# Baropodometro_V3.net
KiCad netlist of a schematic drawn in EAGLE
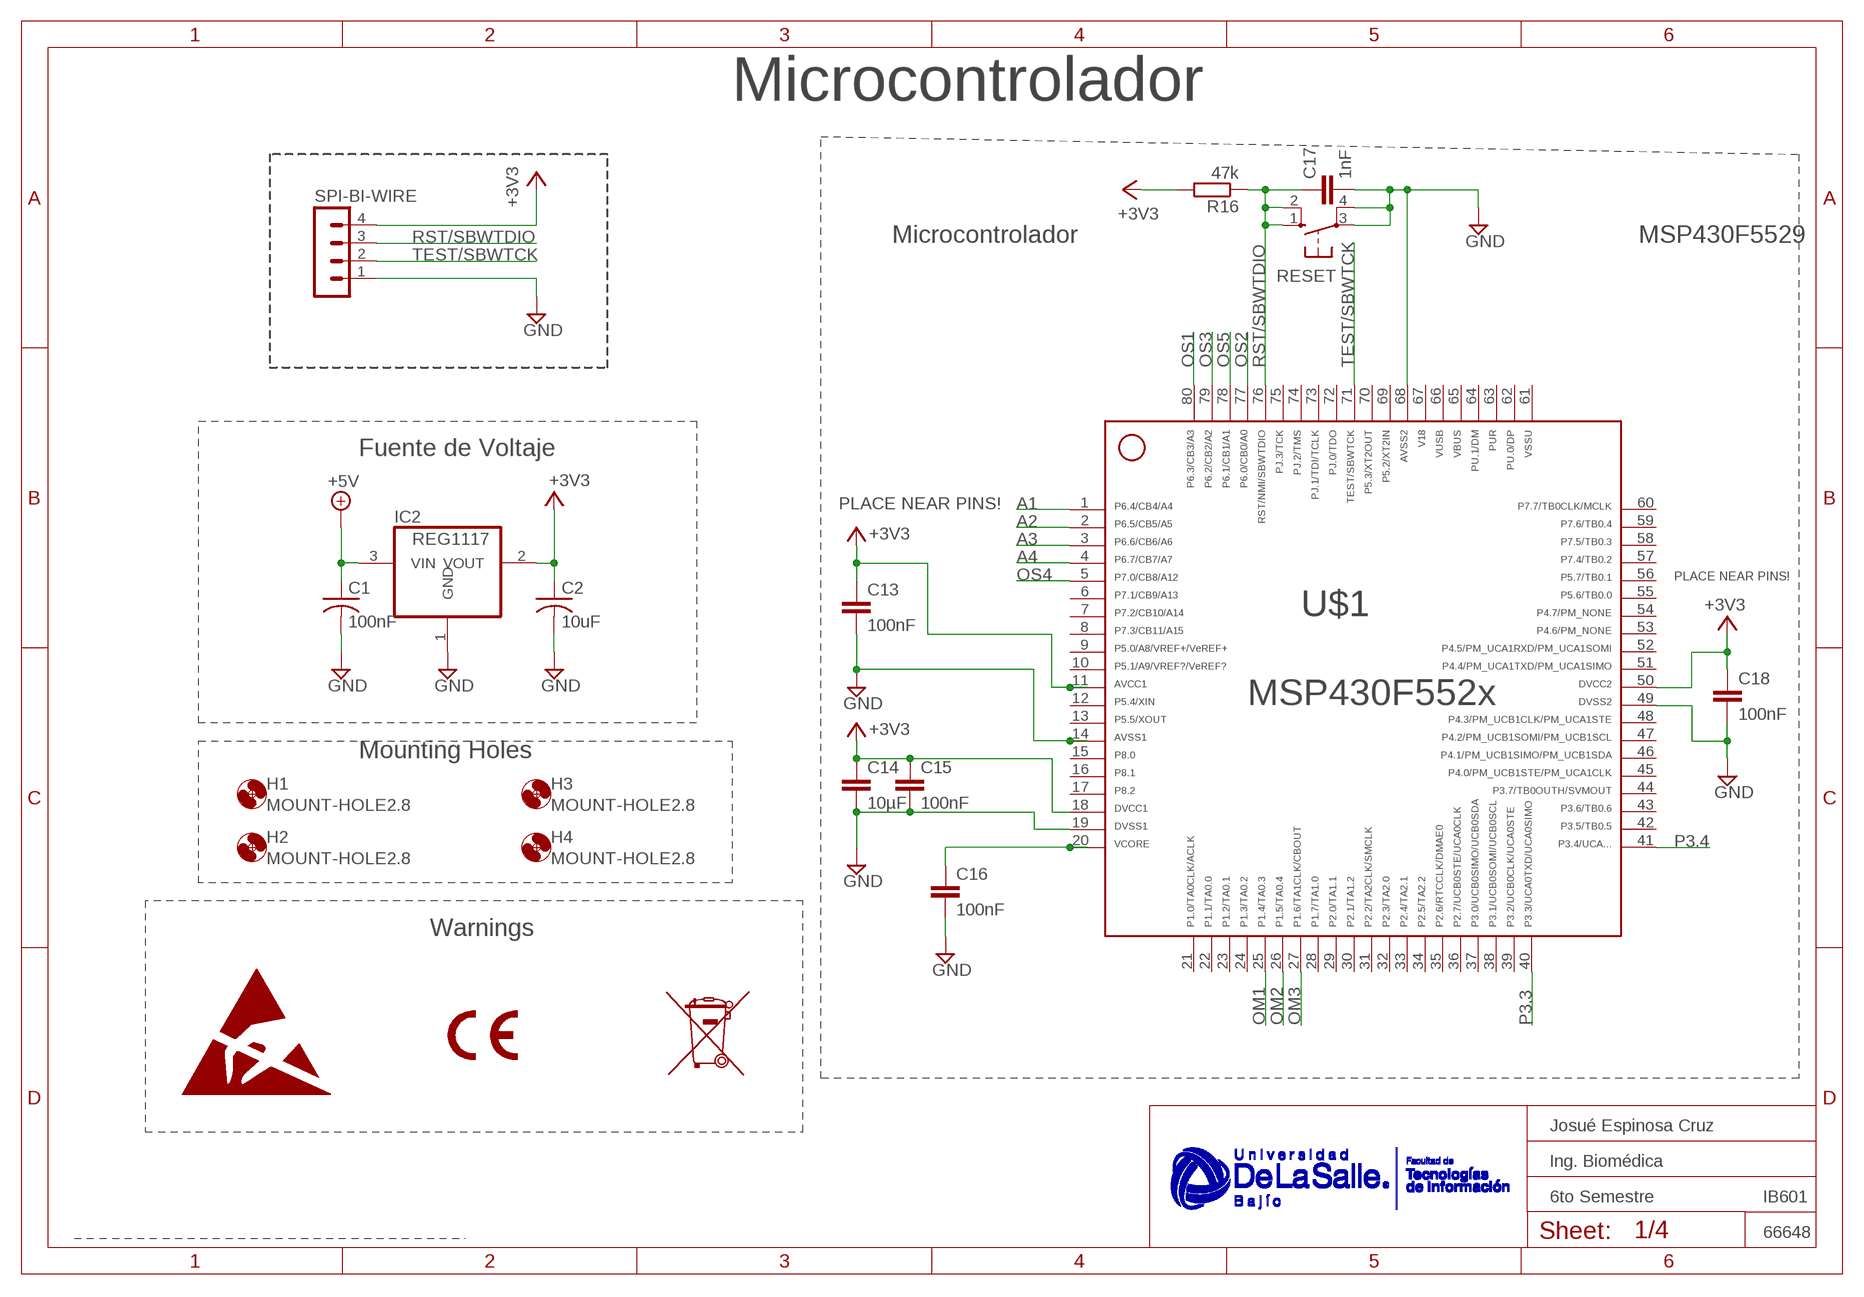
[diagram p0: schematic, sheet 1]
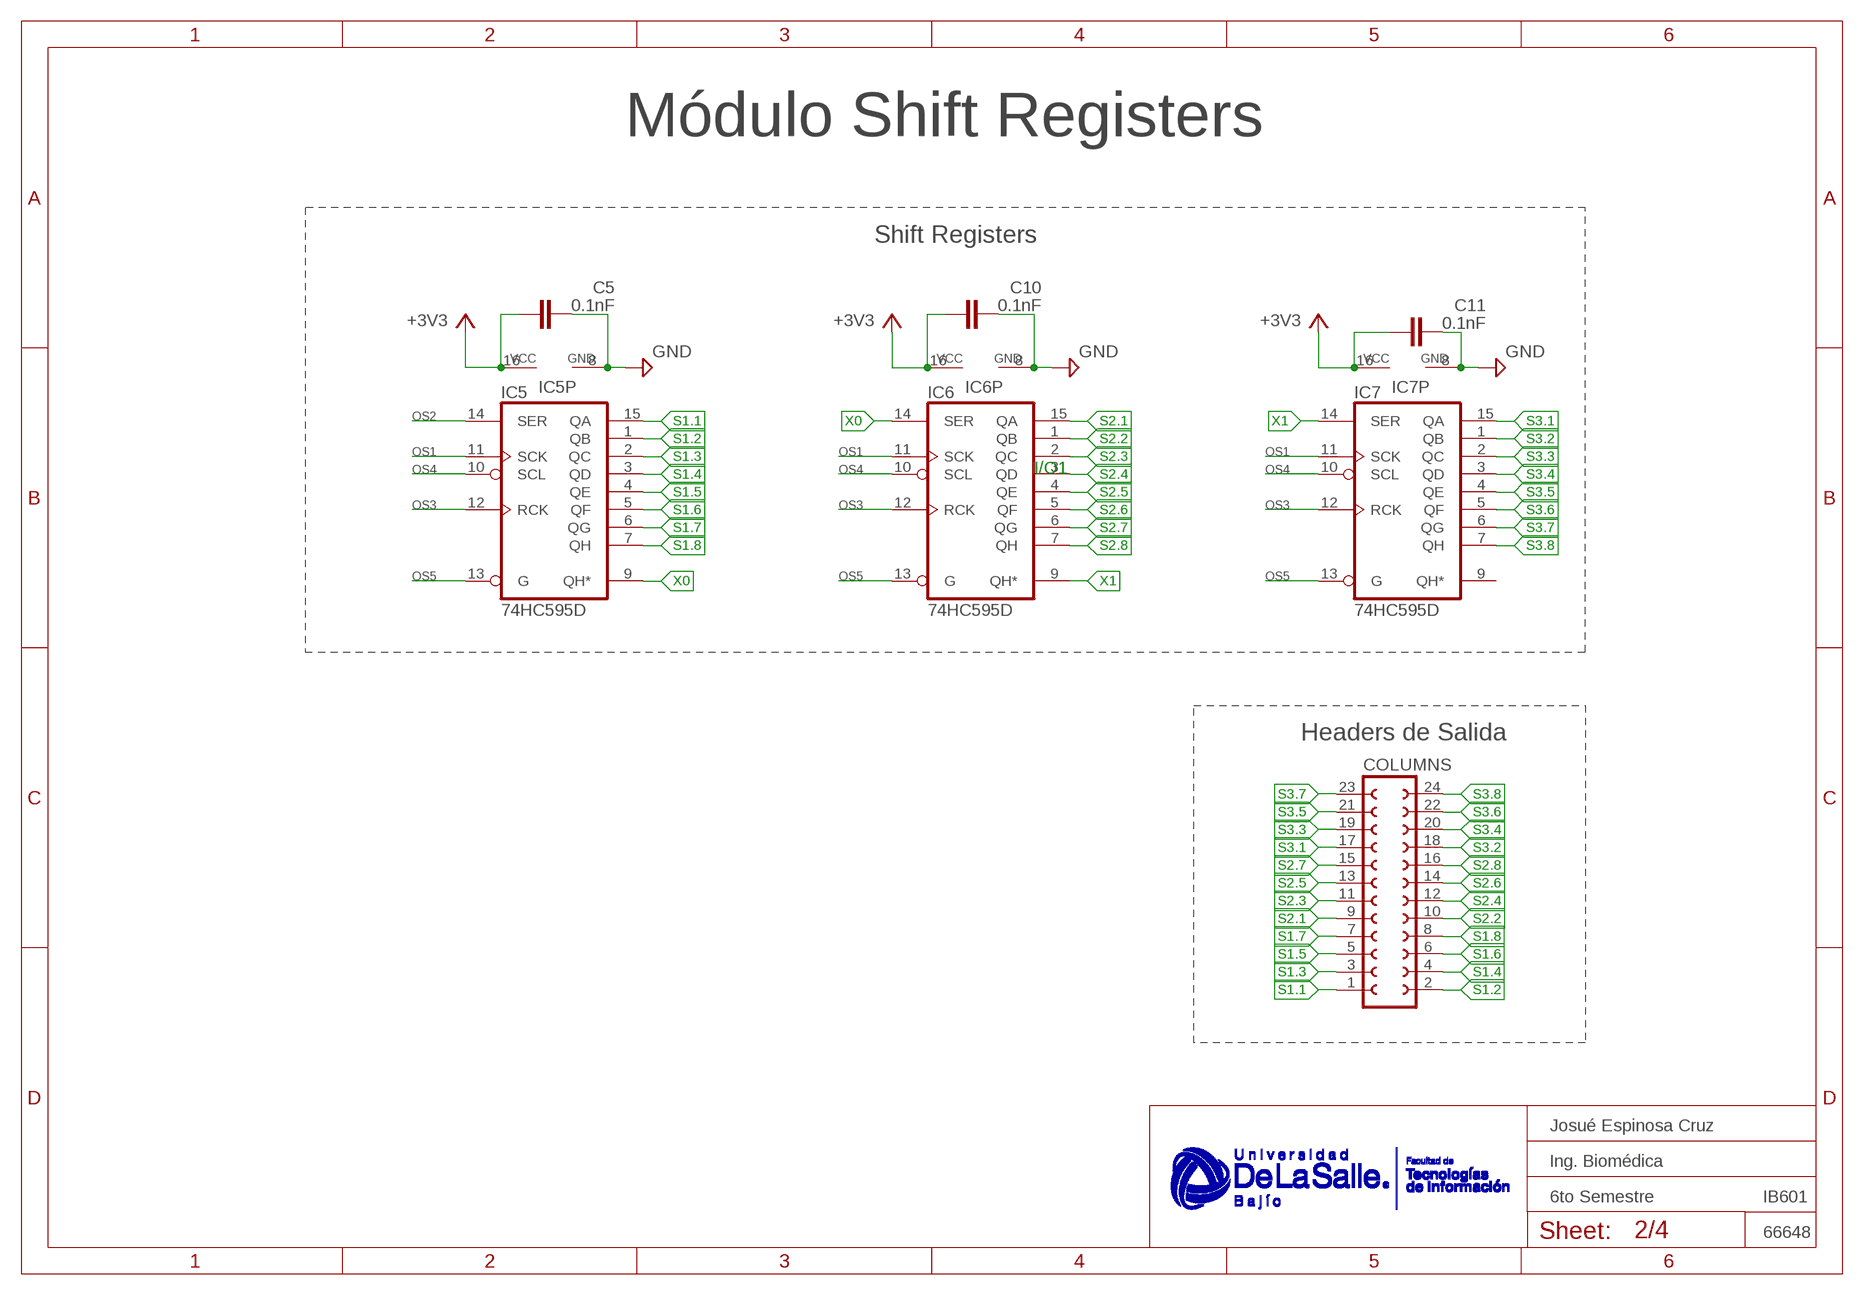
[diagram p1: schematic, sheet 2]
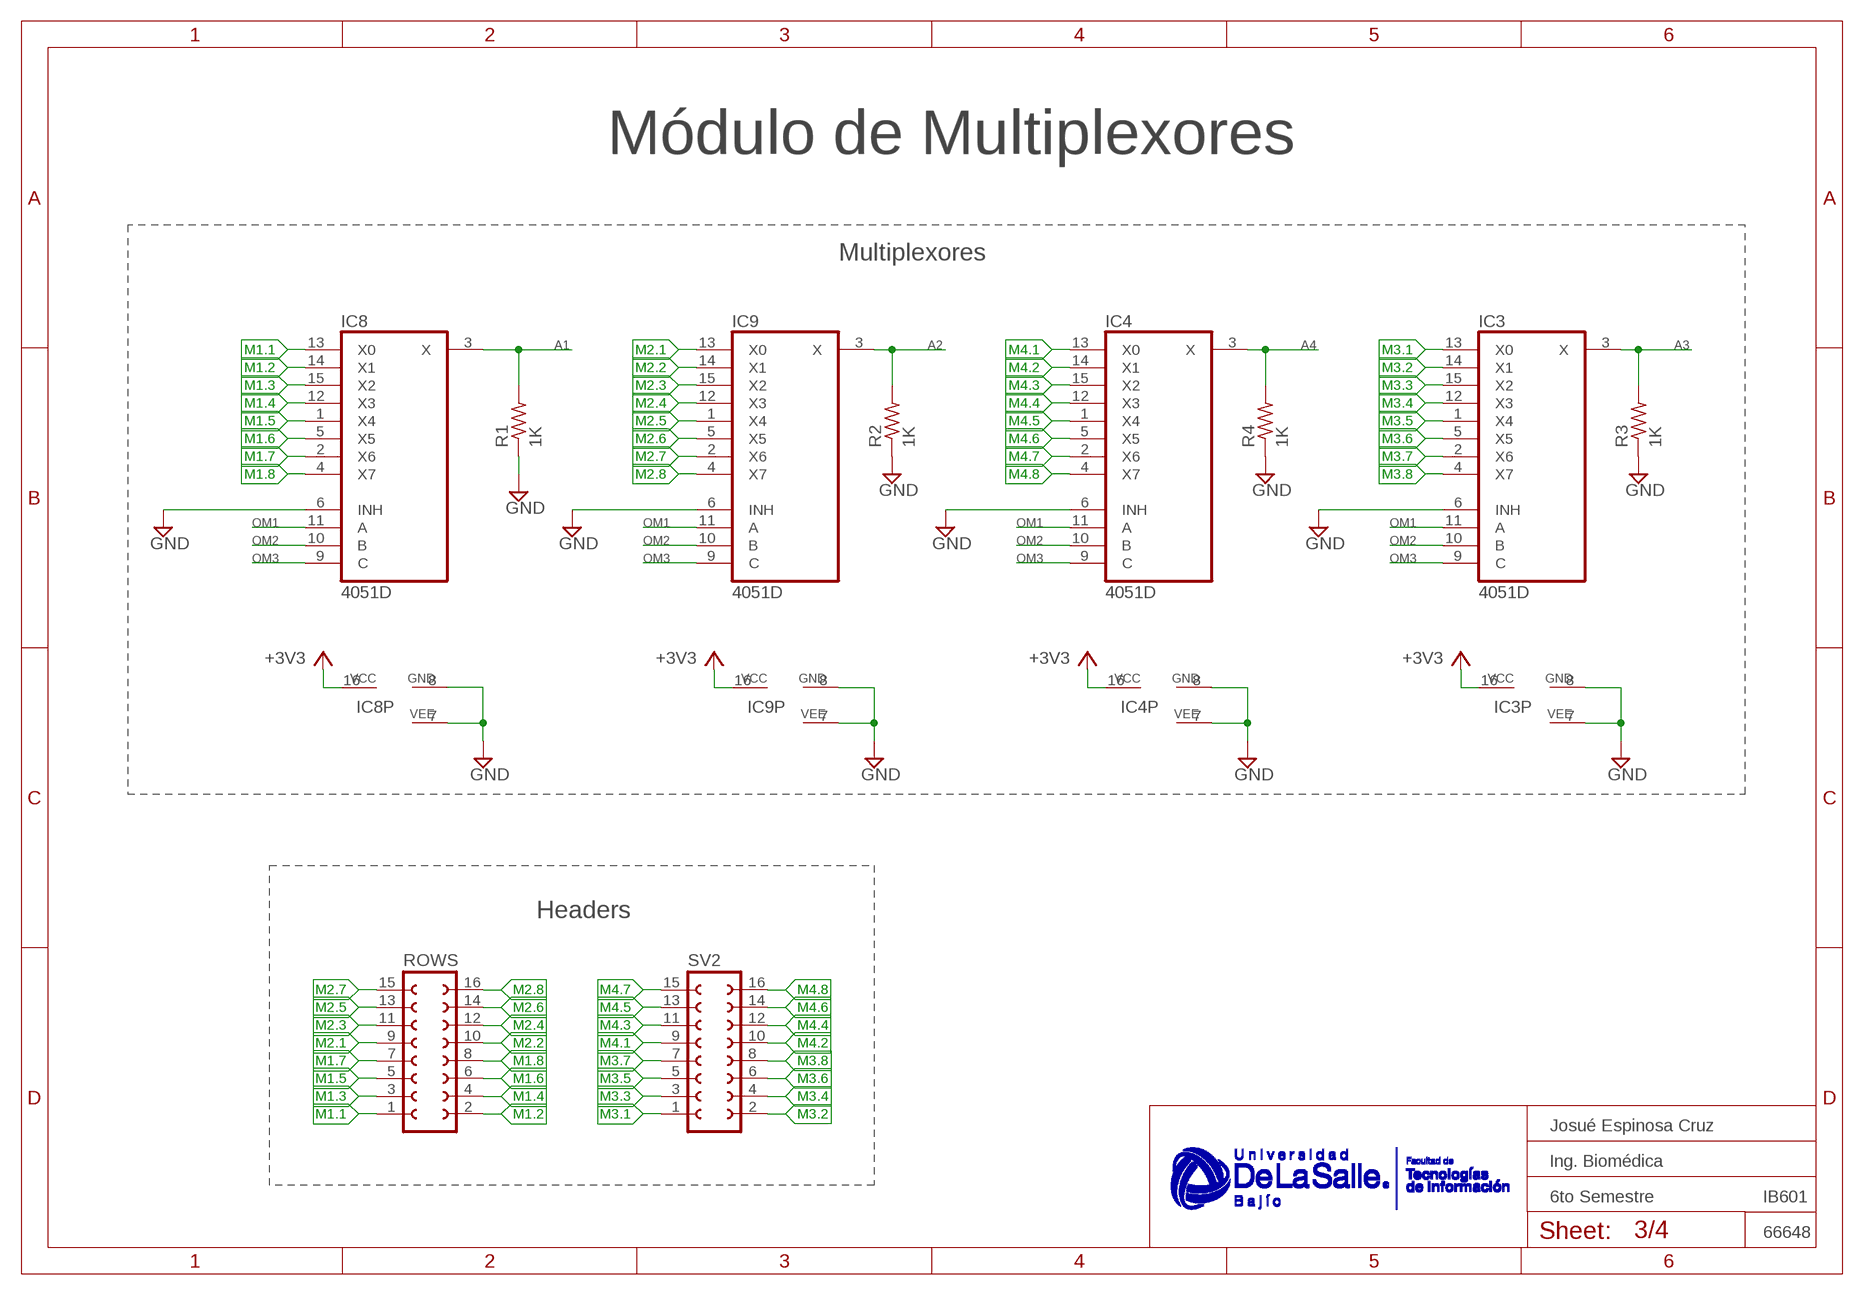
[diagram p2: schematic, sheet 3]
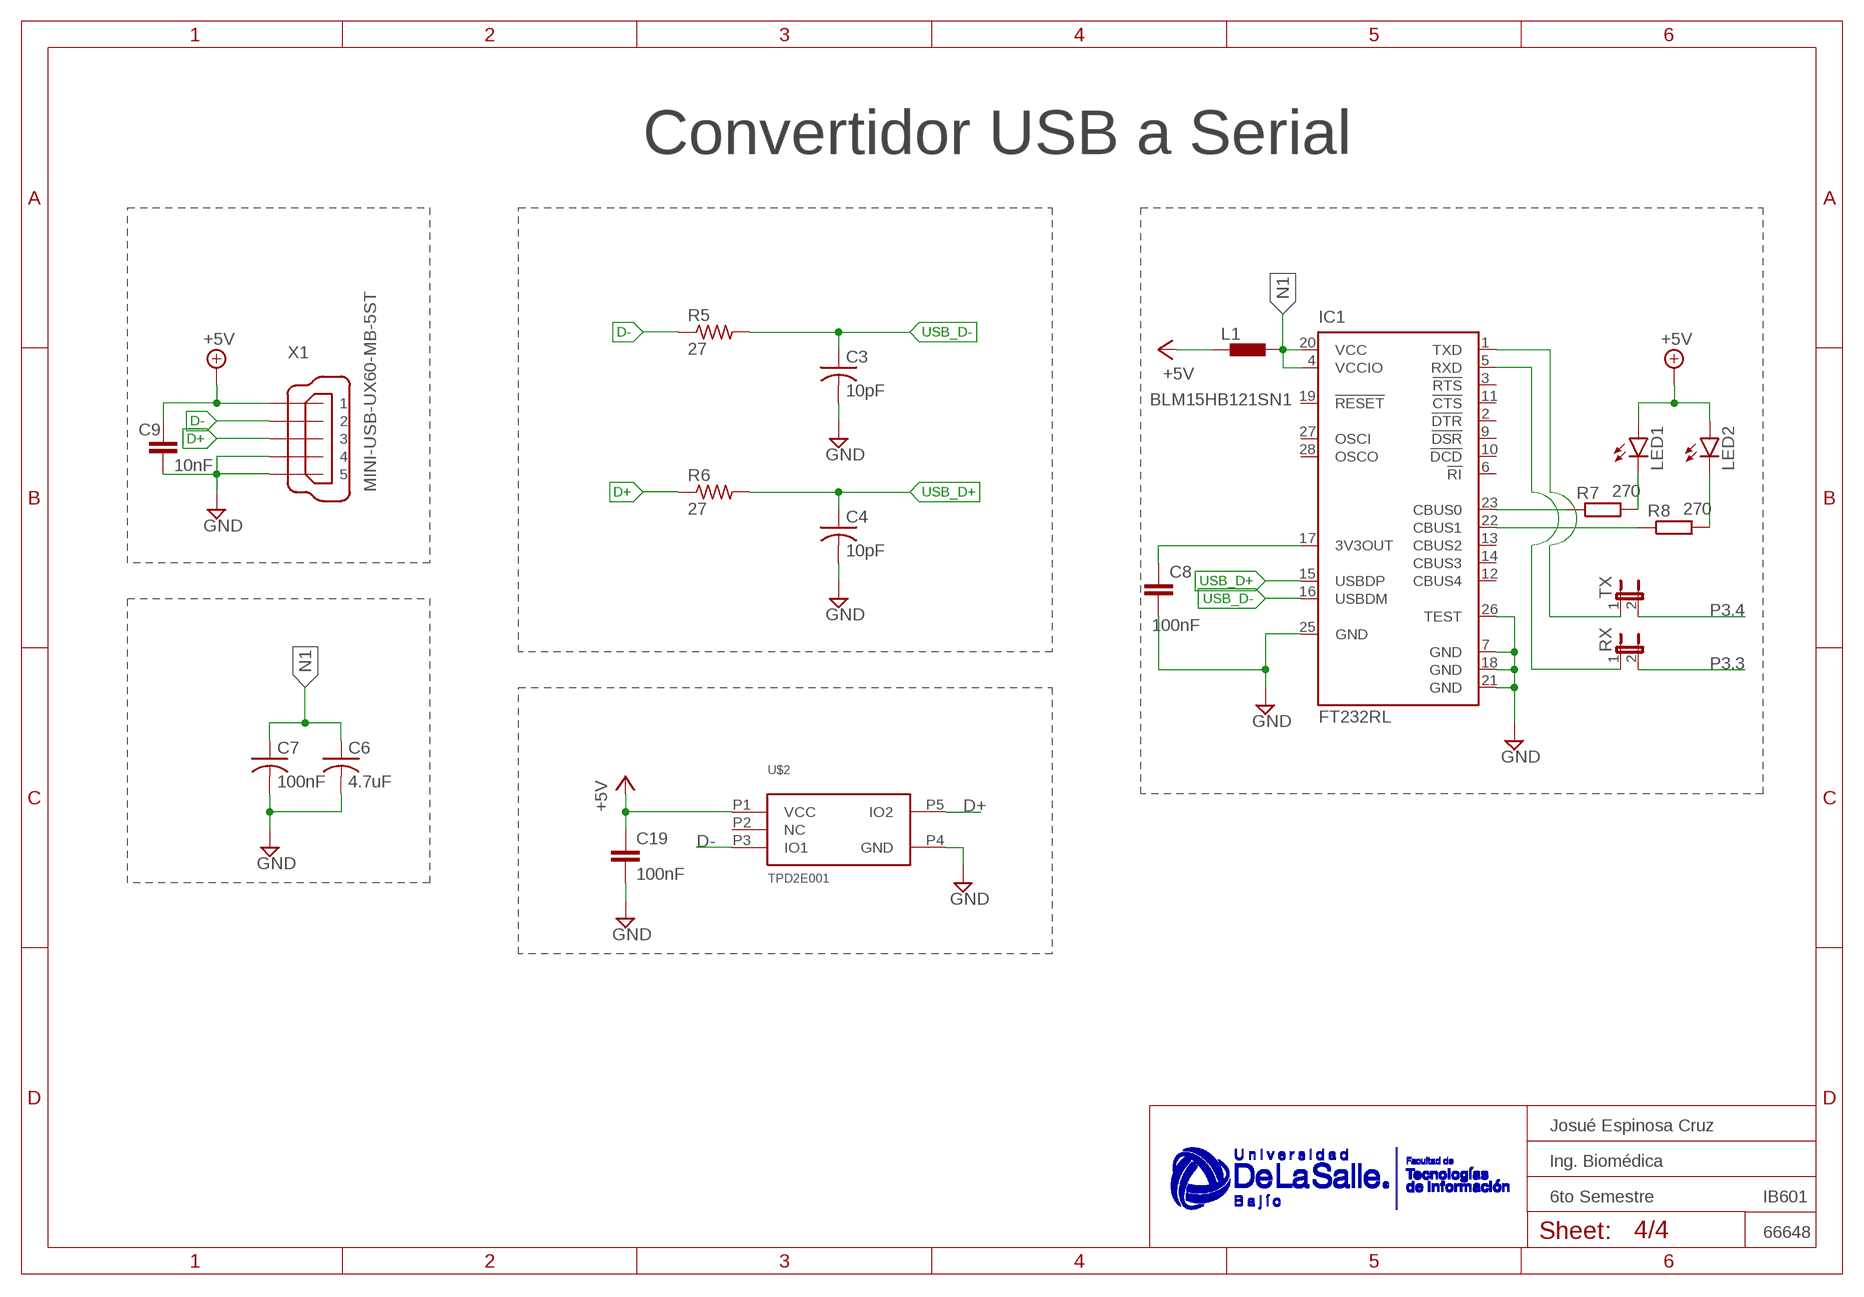
[diagram p3: schematic, sheet 4]

(export (version "E")
  (design (tool "Eeschema 10.0.6"))
  (components
    (comp (ref "C3")
      (value "10pF")
      (footprint "eagle-import:C0805")
      (libsource (lib "eagle-import") (part "C-USC0805"))
    )
    (comp (ref "C4")
      (value "10pF")
      (footprint "eagle-import:C0805")
      (libsource (lib "eagle-import") (part "C-USC0805"))
    )
    (comp (ref "C6")
      (value "4.7uF")
      (footprint "eagle-import:C0805")
      (libsource (lib "eagle-import") (part "C-USC0805"))
    )
    (comp (ref "C7")
      (value "100nF")
      (footprint "eagle-import:C0805")
      (libsource (lib "eagle-import") (part "C-USC0805"))
    )
    (comp (ref "C8")
      (value "100nF")
      (footprint "eagle-import:C0805")
      (libsource (lib "eagle-import") (part "C-EUC0805"))
    )
    (comp (ref "C9")
      (value "10nF")
      (footprint "eagle-import:C0805")
      (libsource (lib "eagle-import") (part "C-EUC0805"))
    )
    (comp (ref "C19")
      (value "100nF")
      (footprint "eagle-import:C0805")
      (libsource (lib "eagle-import") (part "C-EUC0805"))
    )
    (comp (ref "IC1")
      (value "FT232RL")
      (footprint "eagle-import:SSOP28")
      (libsource (lib "eagle-import") (part "FT232RL"))
    )
    (comp (ref "L1")
      (value "BLM15HB121SN1")
      (footprint "eagle-import:0402")
      (libsource (lib "eagle-import") (part "BLM15HB121SN1"))
    )
    (comp (ref "LED1")
      (value "LEDCHIP-LED0805")
      (footprint "eagle-import:CHIP-LED0805")
      (libsource (lib "eagle-import") (part "LEDCHIP-LED0805"))
    )
    (comp (ref "LED2")
      (value "LEDCHIP-LED0805")
      (footprint "eagle-import:CHIP-LED0805")
      (libsource (lib "eagle-import") (part "LEDCHIP-LED0805"))
    )
    (comp (ref "R5")
      (value "27")
      (footprint "eagle-import:R0805")
      (libsource (lib "eagle-import") (part "R-US_R0805"))
    )
    (comp (ref "R6")
      (value "27")
      (footprint "eagle-import:R0805")
      (libsource (lib "eagle-import") (part "R-US_R0805"))
    )
    (comp (ref "R7")
      (value "270")
      (footprint "eagle-import:R0805")
      (libsource (lib "eagle-import") (part "R-EU_R0805"))
    )
    (comp (ref "R8")
      (value "270")
      (footprint "eagle-import:R0805")
      (libsource (lib "eagle-import") (part "R-EU_R0805"))
    )
    (comp (ref "RX")
      (value "JP1E")
      (footprint "eagle-import:JP1")
      (libsource (lib "eagle-import") (part "JP1E"))
    )
    (comp (ref "TX")
      (value "JP1E")
      (footprint "eagle-import:JP1")
      (libsource (lib "eagle-import") (part "JP1E"))
    )
    (comp (ref "U$2")
      (value "TPD2E001")
      (footprint "eagle-import:SOT-5")
      (libsource (lib "eagle-import") (part "TPD2E001"))
    )
    (comp (ref "X1")
      (value "MINI-USB-UX60-MB-5ST")
      (footprint "eagle-import:UX60-MB-5ST")
      (libsource (lib "eagle-import") (part "MINI-USB-UX60-MB-5ST"))
    )
    (comp (ref "C5")
      (value "0.1nF")
      (footprint "eagle-import:C0805")
      (libsource (lib "eagle-import") (part "C-EUC0805"))
    )
    (comp (ref "C10")
      (value "0.1nF")
      (footprint "eagle-import:C0805")
      (libsource (lib "eagle-import") (part "C-EUC0805"))
    )
    (comp (ref "C11")
      (value "0.1nF")
      (footprint "eagle-import:C0805")
      (libsource (lib "eagle-import") (part "C-EUC0805"))
    )
    (comp (ref "COLUMNS")
      (value "FE12-2W")
      (footprint "eagle-import:FE12-2W")
      (libsource (lib "eagle-import") (part "FE12-2W"))
    )
    (comp (ref "IC5")
      (value "74HC595D")
      (footprint "eagle-import:SO16")
      (libsource (lib "eagle-import") (part "74595DHC"))
    )
    (comp (ref "IC6")
      (value "74HC595D")
      (footprint "eagle-import:SO16")
      (libsource (lib "eagle-import") (part "74595DHC"))
    )
    (comp (ref "IC7")
      (value "74HC595D")
      (footprint "eagle-import:SO16")
      (libsource (lib "eagle-import") (part "74595DHC"))
    )
    (comp (ref "C1")
      (value "100nF")
      (footprint "eagle-import:C0805")
      (libsource (lib "eagle-import") (part "C-USC0805"))
    )
    (comp (ref "C2")
      (value "10uF")
      (footprint "eagle-import:C0805")
      (libsource (lib "eagle-import") (part "C-USC0805"))
    )
    (comp (ref "C13")
      (value "100nF")
      (footprint "eagle-import:C0805")
      (libsource (lib "eagle-import") (part "C-EUC0805"))
    )
    (comp (ref "C14")
      (value "10µF")
      (footprint "eagle-import:C0805")
      (libsource (lib "eagle-import") (part "C-EUC0805"))
    )
    (comp (ref "C15")
      (value "100nF")
      (footprint "eagle-import:C0805")
      (libsource (lib "eagle-import") (part "C-EUC0805"))
    )
    (comp (ref "C16")
      (value "100nF")
      (footprint "eagle-import:C0805")
      (libsource (lib "eagle-import") (part "C-EUC0805"))
    )
    (comp (ref "C17")
      (value "1nF")
      (footprint "eagle-import:C0805")
      (libsource (lib "eagle-import") (part "C-EUC0805"))
    )
    (comp (ref "C18")
      (value "100nF")
      (footprint "eagle-import:C0805")
      (libsource (lib "eagle-import") (part "C-EUC0805"))
    )
    (comp (ref "H1")
      (value "MOUNT-HOLE2.8")
      (footprint "eagle-import:2,8")
      (libsource (lib "eagle-import") (part "MOUNT-HOLE2.8"))
    )
    (comp (ref "H2")
      (value "MOUNT-HOLE2.8")
      (footprint "eagle-import:2,8")
      (libsource (lib "eagle-import") (part "MOUNT-HOLE2.8"))
    )
    (comp (ref "H3")
      (value "MOUNT-HOLE2.8")
      (footprint "eagle-import:2,8")
      (libsource (lib "eagle-import") (part "MOUNT-HOLE2.8"))
    )
    (comp (ref "H4")
      (value "MOUNT-HOLE2.8")
      (footprint "eagle-import:2,8")
      (libsource (lib "eagle-import") (part "MOUNT-HOLE2.8"))
    )
    (comp (ref "IC2")
      (value "REG1117")
      (footprint "eagle-import:SOT223")
      (libsource (lib "eagle-import") (part "REG1117"))
    )
    (comp (ref "R16")
      (value "47k")
      (footprint "eagle-import:R0805")
      (libsource (lib "eagle-import") (part "R-EU_R0805"))
    )
    (comp (ref "RESET")
      (value "10-XX")
      (footprint "eagle-import:B3F-10XX")
      (fields (field (name "MPN") "B3F-1000"))
      (libsource (lib "eagle-import") (part "10-XX"))
    )
    (comp (ref "SPI-BI-WIRE")
      (value "MA04-1")
      (footprint "eagle-import:MA04-1")
      (libsource (lib "eagle-import") (part "MA04-1"))
    )
    (comp (ref "U$1")
      (value "MSP430F5529")
      (footprint "eagle-import:TI_MSP430_V16_INTERN_PN80")
      (libsource (lib "eagle-import") (part "TI_MSP430_V16_INTERN_F552X---PN80"))
    )
    (comp (ref "IC3")
      (value "4051D")
      (footprint "eagle-import:SO16")
      (libsource (lib "eagle-import") (part "4051D"))
    )
    (comp (ref "IC4")
      (value "4051D")
      (footprint "eagle-import:SO16")
      (libsource (lib "eagle-import") (part "4051D"))
    )
    (comp (ref "IC8")
      (value "4051D")
      (footprint "eagle-import:SO16")
      (libsource (lib "eagle-import") (part "4051D"))
    )
    (comp (ref "IC9")
      (value "4051D")
      (footprint "eagle-import:SO16")
      (libsource (lib "eagle-import") (part "4051D"))
    )
    (comp (ref "R1")
      (value "1K")
      (footprint "eagle-import:R0805")
      (libsource (lib "eagle-import") (part "R-US_R0805"))
    )
    (comp (ref "R2")
      (value "1K")
      (footprint "eagle-import:R0805")
      (libsource (lib "eagle-import") (part "R-US_R0805"))
    )
    (comp (ref "R3")
      (value "1K")
      (footprint "eagle-import:R0805")
      (libsource (lib "eagle-import") (part "R-US_R0805"))
    )
    (comp (ref "R4")
      (value "1K")
      (footprint "eagle-import:R0805")
      (libsource (lib "eagle-import") (part "R-US_R0805"))
    )
    (comp (ref "ROWS")
      (value "FE08-2W")
      (footprint "eagle-import:FE08-2W")
      (libsource (lib "eagle-import") (part "FE08-2W"))
    )
    (comp (ref "SV2")
      (value "FE08-2W")
      (footprint "eagle-import:FE08-2W")
      (libsource (lib "eagle-import") (part "FE08-2W"))
    )
  )
  (nets
    (net (code "1") (name "+3V3") (class "Default")
      (node (ref "C10") (pin "1") (pinfunction "1_1") (pintype "passive"))
      (node (ref "C11") (pin "1") (pinfunction "1_1") (pintype "passive"))
      (node (ref "C13") (pin "1") (pinfunction "1_1") (pintype "passive"))
      (node (ref "C14") (pin "1") (pinfunction "1_1") (pintype "passive"))
      (node (ref "C15") (pin "1") (pinfunction "1_1") (pintype "passive"))
      (node (ref "C18") (pin "1") (pinfunction "1_1") (pintype "passive"))
      (node (ref "C2") (pin "1") (pinfunction "1_1") (pintype "passive"))
      (node (ref "C5") (pin "1") (pinfunction "1_1") (pintype "passive"))
      (node (ref "IC2") (pin "2") (pinfunction "VOUT_2") (pintype "output"))
      (node (ref "IC3") (pin "16") (pinfunction "VCC_16") (pintype "power_in"))
      (node (ref "IC4") (pin "16") (pinfunction "VCC_16") (pintype "power_in"))
      (node (ref "IC5") (pin "16") (pinfunction "VCC_16") (pintype "power_in"))
      (node (ref "IC6") (pin "16") (pinfunction "VCC_16") (pintype "power_in"))
      (node (ref "IC7") (pin "16") (pinfunction "VCC_16") (pintype "power_in"))
      (node (ref "IC8") (pin "16") (pinfunction "VCC_16") (pintype "power_in"))
      (node (ref "IC9") (pin "16") (pinfunction "VCC_16") (pintype "power_in"))
      (node (ref "R16") (pin "2") (pinfunction "2_2") (pintype "passive"))
      (node (ref "SPI-BI-WIRE") (pin "4") (pinfunction "4_4") (pintype "passive"))
      (node (ref "U$1") (pin "11") (pinfunction "11_11") (pintype "power_in"))
      (node (ref "U$1") (pin "18") (pinfunction "18_18") (pintype "power_in"))
      (node (ref "U$1") (pin "50") (pinfunction "50_50") (pintype "power_in"))
    )
    (net (code "2") (name "+5V") (class "Default")
      (node (ref "C1") (pin "1") (pinfunction "1_1") (pintype "passive"))
      (node (ref "C19") (pin "1") (pinfunction "1_1") (pintype "passive"))
      (node (ref "C9") (pin "1") (pinfunction "1_1") (pintype "passive"))
      (node (ref "IC2") (pin "3") (pinfunction "VIN_3") (pintype "input"))
      (node (ref "L1") (pin "1") (pinfunction "1_1") (pintype "passive"))
      (node (ref "LED1") (pin "A") (pinfunction "A_A") (pintype "passive"))
      (node (ref "LED2") (pin "A") (pinfunction "A_A") (pintype "passive"))
      (node (ref "U$2") (pin "P1") (pinfunction "VCC_P1") (pintype "bidirectional"))
      (node (ref "X1") (pin "1") (pinfunction "1_1") (pintype "input"))
    )
    (net (code "3") (name "61") (class "Default")
      (node (ref "U$1") (pin "61") (pinfunction "61_61") (pintype "power_in"))
    )
    (net (code "4") (name "65") (class "Default")
      (node (ref "U$1") (pin "65") (pinfunction "65_65") (pintype "power_in"))
    )
    (net (code "5") (name "66") (class "Default")
      (node (ref "U$1") (pin "66") (pinfunction "66_66") (pintype "power_in"))
    )
    (net (code "6") (name "67") (class "Default")
      (node (ref "U$1") (pin "67") (pinfunction "67_67") (pintype "power_in"))
    )
    (net (code "7") (name "A1") (class "Default")
      (node (ref "IC8") (pin "3") (pinfunction "X_3") (pintype "bidirectional"))
      (node (ref "R1") (pin "2") (pinfunction "2_2") (pintype "passive"))
      (node (ref "U$1") (pin "1") (pinfunction "1_1") (pintype "bidirectional"))
    )
    (net (code "8") (name "A2") (class "Default")
      (node (ref "IC9") (pin "3") (pinfunction "X_3") (pintype "bidirectional"))
      (node (ref "R2") (pin "2") (pinfunction "2_2") (pintype "passive"))
      (node (ref "U$1") (pin "2") (pinfunction "2_2") (pintype "bidirectional"))
    )
    (net (code "9") (name "A3") (class "Default")
      (node (ref "IC3") (pin "3") (pinfunction "X_3") (pintype "bidirectional"))
      (node (ref "R3") (pin "2") (pinfunction "2_2") (pintype "passive"))
      (node (ref "U$1") (pin "3") (pinfunction "3_3") (pintype "bidirectional"))
    )
    (net (code "10") (name "A4") (class "Default")
      (node (ref "IC4") (pin "3") (pinfunction "X_3") (pintype "bidirectional"))
      (node (ref "R4") (pin "2") (pinfunction "2_2") (pintype "passive"))
      (node (ref "U$1") (pin "4") (pinfunction "4_4") (pintype "bidirectional"))
    )
    (net (code "11") (name "D+") (class "Default")
      (node (ref "R6") (pin "1") (pinfunction "1_1") (pintype "passive"))
      (node (ref "U$2") (pin "P5") (pinfunction "IO2_P5") (pintype "bidirectional"))
      (node (ref "X1") (pin "3") (pinfunction "3_3") (pintype "input"))
    )
    (net (code "12") (name "D-") (class "Default")
      (node (ref "R5") (pin "1") (pinfunction "1_1") (pintype "passive"))
      (node (ref "U$2") (pin "P3") (pinfunction "IO1_P3") (pintype "bidirectional"))
      (node (ref "X1") (pin "2") (pinfunction "2_2") (pintype "input"))
    )
    (net (code "13") (name "GND") (class "Default")
      (node (ref "C1") (pin "2") (pinfunction "2_2") (pintype "passive"))
      (node (ref "C10") (pin "2") (pinfunction "2_2") (pintype "passive"))
      (node (ref "C11") (pin "2") (pinfunction "2_2") (pintype "passive"))
      (node (ref "C13") (pin "2") (pinfunction "2_2") (pintype "passive"))
      (node (ref "C14") (pin "2") (pinfunction "2_2") (pintype "passive"))
      (node (ref "C15") (pin "2") (pinfunction "2_2") (pintype "passive"))
      (node (ref "C16") (pin "2") (pinfunction "2_2") (pintype "passive"))
      (node (ref "C17") (pin "2") (pinfunction "2_2") (pintype "passive"))
      (node (ref "C18") (pin "2") (pinfunction "2_2") (pintype "passive"))
      (node (ref "C19") (pin "2") (pinfunction "2_2") (pintype "passive"))
      (node (ref "C2") (pin "2") (pinfunction "2_2") (pintype "passive"))
      (node (ref "C3") (pin "2") (pinfunction "2_2") (pintype "passive"))
      (node (ref "C4") (pin "2") (pinfunction "2_2") (pintype "passive"))
      (node (ref "C5") (pin "2") (pinfunction "2_2") (pintype "passive"))
      (node (ref "C6") (pin "2") (pinfunction "2_2") (pintype "passive"))
      (node (ref "C7") (pin "2") (pinfunction "2_2") (pintype "passive"))
      (node (ref "C8") (pin "2") (pinfunction "2_2") (pintype "passive"))
      (node (ref "C9") (pin "2") (pinfunction "2_2") (pintype "passive"))
      (node (ref "IC1") (pin "18") (pinfunction "GND_18") (pintype "power_in"))
      (node (ref "IC1") (pin "21") (pinfunction "GND_21") (pintype "power_in"))
      (node (ref "IC1") (pin "25") (pinfunction "GND_25") (pintype "power_in"))
      (node (ref "IC1") (pin "26") (pinfunction "TEST_26") (pintype "input"))
      (node (ref "IC1") (pin "7") (pinfunction "GND_7") (pintype "power_in"))
      (node (ref "IC2") (pin "1") (pinfunction "GND_1") (pintype "power_in"))
      (node (ref "IC3") (pin "6") (pinfunction "INH_6") (pintype "input"))
      (node (ref "IC3") (pin "7") (pinfunction "VEE_7") (pintype "power_in"))
      (node (ref "IC3") (pin "8") (pinfunction "GND_8") (pintype "power_in"))
      (node (ref "IC4") (pin "6") (pinfunction "INH_6") (pintype "input"))
      (node (ref "IC4") (pin "7") (pinfunction "VEE_7") (pintype "power_in"))
      (node (ref "IC4") (pin "8") (pinfunction "GND_8") (pintype "power_in"))
      (node (ref "IC5") (pin "8") (pinfunction "GND_8") (pintype "power_in"))
      (node (ref "IC6") (pin "8") (pinfunction "GND_8") (pintype "power_in"))
      (node (ref "IC7") (pin "8") (pinfunction "GND_8") (pintype "power_in"))
      (node (ref "IC8") (pin "6") (pinfunction "INH_6") (pintype "input"))
      (node (ref "IC8") (pin "7") (pinfunction "VEE_7") (pintype "power_in"))
      (node (ref "IC8") (pin "8") (pinfunction "GND_8") (pintype "power_in"))
      (node (ref "IC9") (pin "6") (pinfunction "INH_6") (pintype "input"))
      (node (ref "IC9") (pin "7") (pinfunction "VEE_7") (pintype "power_in"))
      (node (ref "IC9") (pin "8") (pinfunction "GND_8") (pintype "power_in"))
      (node (ref "R1") (pin "1") (pinfunction "1_1") (pintype "passive"))
      (node (ref "R2") (pin "1") (pinfunction "1_1") (pintype "passive"))
      (node (ref "R3") (pin "1") (pinfunction "1_1") (pintype "passive"))
      (node (ref "R4") (pin "1") (pinfunction "1_1") (pintype "passive"))
      (node (ref "RESET") (pin "3") (pinfunction "P_3") (pintype "passive"))
      (node (ref "RESET") (pin "4") (pinfunction "P1_4") (pintype "passive"))
      (node (ref "SPI-BI-WIRE") (pin "1") (pinfunction "1_1") (pintype "passive"))
      (node (ref "U$1") (pin "14") (pinfunction "14_14") (pintype "power_in"))
      (node (ref "U$1") (pin "19") (pinfunction "19_19") (pintype "power_in"))
      (node (ref "U$1") (pin "49") (pinfunction "49_49") (pintype "power_in"))
      (node (ref "U$1") (pin "68") (pinfunction "68_68") (pintype "power_in"))
      (node (ref "U$2") (pin "P4") (pinfunction "GND_P4") (pintype "bidirectional"))
      (node (ref "X1") (pin "4") (pinfunction "4_4") (pintype "input"))
      (node (ref "X1") (pin "5") (pinfunction "5_5") (pintype "input"))
    )
    (net (code "14") (name "M1.1") (class "Default")
      (node (ref "IC8") (pin "13") (pinfunction "X0_13") (pintype "bidirectional"))
      (node (ref "ROWS") (pin "1") (pinfunction "1_1") (pintype "passive"))
    )
    (net (code "15") (name "M1.2") (class "Default")
      (node (ref "IC8") (pin "14") (pinfunction "X1_14") (pintype "bidirectional"))
      (node (ref "ROWS") (pin "2") (pinfunction "2_2") (pintype "passive"))
    )
    (net (code "16") (name "M1.3") (class "Default")
      (node (ref "IC8") (pin "15") (pinfunction "X2_15") (pintype "bidirectional"))
      (node (ref "ROWS") (pin "3") (pinfunction "3_3") (pintype "passive"))
    )
    (net (code "17") (name "M1.4") (class "Default")
      (node (ref "IC8") (pin "12") (pinfunction "X3_12") (pintype "bidirectional"))
      (node (ref "ROWS") (pin "4") (pinfunction "4_4") (pintype "passive"))
    )
    (net (code "18") (name "M1.5") (class "Default")
      (node (ref "IC8") (pin "1") (pinfunction "X4_1") (pintype "bidirectional"))
      (node (ref "ROWS") (pin "5") (pinfunction "5_5") (pintype "passive"))
    )
    (net (code "19") (name "M1.6") (class "Default")
      (node (ref "IC8") (pin "5") (pinfunction "X5_5") (pintype "bidirectional"))
      (node (ref "ROWS") (pin "6") (pinfunction "6_6") (pintype "passive"))
    )
    (net (code "20") (name "M1.7") (class "Default")
      (node (ref "IC8") (pin "2") (pinfunction "X6_2") (pintype "bidirectional"))
      (node (ref "ROWS") (pin "7") (pinfunction "7_7") (pintype "passive"))
    )
    (net (code "21") (name "M1.8") (class "Default")
      (node (ref "IC8") (pin "4") (pinfunction "X7_4") (pintype "bidirectional"))
      (node (ref "ROWS") (pin "8") (pinfunction "8_8") (pintype "passive"))
    )
    (net (code "22") (name "M2.1") (class "Default")
      (node (ref "IC9") (pin "13") (pinfunction "X0_13") (pintype "bidirectional"))
      (node (ref "ROWS") (pin "9") (pinfunction "9_9") (pintype "passive"))
    )
    (net (code "23") (name "M2.2") (class "Default")
      (node (ref "IC9") (pin "14") (pinfunction "X1_14") (pintype "bidirectional"))
      (node (ref "ROWS") (pin "10") (pinfunction "10_10") (pintype "passive"))
    )
    (net (code "24") (name "M2.3") (class "Default")
      (node (ref "IC9") (pin "15") (pinfunction "X2_15") (pintype "bidirectional"))
      (node (ref "ROWS") (pin "11") (pinfunction "11_11") (pintype "passive"))
    )
    (net (code "25") (name "M2.4") (class "Default")
      (node (ref "IC9") (pin "12") (pinfunction "X3_12") (pintype "bidirectional"))
      (node (ref "ROWS") (pin "12") (pinfunction "12_12") (pintype "passive"))
    )
    (net (code "26") (name "M2.5") (class "Default")
      (node (ref "IC9") (pin "1") (pinfunction "X4_1") (pintype "bidirectional"))
      (node (ref "ROWS") (pin "13") (pinfunction "13_13") (pintype "passive"))
    )
    (net (code "27") (name "M2.6") (class "Default")
      (node (ref "IC9") (pin "5") (pinfunction "X5_5") (pintype "bidirectional"))
      (node (ref "ROWS") (pin "14") (pinfunction "14_14") (pintype "passive"))
    )
    (net (code "28") (name "M2.7") (class "Default")
      (node (ref "IC9") (pin "2") (pinfunction "X6_2") (pintype "bidirectional"))
      (node (ref "ROWS") (pin "15") (pinfunction "15_15") (pintype "passive"))
    )
    (net (code "29") (name "M2.8") (class "Default")
      (node (ref "IC9") (pin "4") (pinfunction "X7_4") (pintype "bidirectional"))
      (node (ref "ROWS") (pin "16") (pinfunction "16_16") (pintype "passive"))
    )
    (net (code "30") (name "M3.1") (class "Default")
      (node (ref "IC3") (pin "13") (pinfunction "X0_13") (pintype "bidirectional"))
      (node (ref "SV2") (pin "1") (pinfunction "1_1") (pintype "passive"))
    )
    (net (code "31") (name "M3.2") (class "Default")
      (node (ref "IC3") (pin "14") (pinfunction "X1_14") (pintype "bidirectional"))
      (node (ref "SV2") (pin "2") (pinfunction "2_2") (pintype "passive"))
    )
    (net (code "32") (name "M3.3") (class "Default")
      (node (ref "IC3") (pin "15") (pinfunction "X2_15") (pintype "bidirectional"))
      (node (ref "SV2") (pin "3") (pinfunction "3_3") (pintype "passive"))
    )
    (net (code "33") (name "M3.4") (class "Default")
      (node (ref "IC3") (pin "12") (pinfunction "X3_12") (pintype "bidirectional"))
      (node (ref "SV2") (pin "4") (pinfunction "4_4") (pintype "passive"))
    )
    (net (code "34") (name "M3.5") (class "Default")
      (node (ref "IC3") (pin "1") (pinfunction "X4_1") (pintype "bidirectional"))
      (node (ref "SV2") (pin "5") (pinfunction "5_5") (pintype "passive"))
    )
    (net (code "35") (name "M3.6") (class "Default")
      (node (ref "IC3") (pin "5") (pinfunction "X5_5") (pintype "bidirectional"))
      (node (ref "SV2") (pin "6") (pinfunction "6_6") (pintype "passive"))
    )
    (net (code "36") (name "M3.7") (class "Default")
      (node (ref "IC3") (pin "2") (pinfunction "X6_2") (pintype "bidirectional"))
      (node (ref "SV2") (pin "7") (pinfunction "7_7") (pintype "passive"))
    )
    (net (code "37") (name "M3.8") (class "Default")
      (node (ref "IC3") (pin "4") (pinfunction "X7_4") (pintype "bidirectional"))
      (node (ref "SV2") (pin "8") (pinfunction "8_8") (pintype "passive"))
    )
    (net (code "38") (name "M4.1") (class "Default")
      (node (ref "IC4") (pin "13") (pinfunction "X0_13") (pintype "bidirectional"))
      (node (ref "SV2") (pin "9") (pinfunction "9_9") (pintype "passive"))
    )
    (net (code "39") (name "M4.2") (class "Default")
      (node (ref "IC4") (pin "14") (pinfunction "X1_14") (pintype "bidirectional"))
      (node (ref "SV2") (pin "10") (pinfunction "10_10") (pintype "passive"))
    )
    (net (code "40") (name "M4.3") (class "Default")
      (node (ref "IC4") (pin "15") (pinfunction "X2_15") (pintype "bidirectional"))
      (node (ref "SV2") (pin "11") (pinfunction "11_11") (pintype "passive"))
    )
    (net (code "41") (name "M4.4") (class "Default")
      (node (ref "IC4") (pin "12") (pinfunction "X3_12") (pintype "bidirectional"))
      (node (ref "SV2") (pin "12") (pinfunction "12_12") (pintype "passive"))
    )
    (net (code "42") (name "M4.5") (class "Default")
      (node (ref "IC4") (pin "1") (pinfunction "X4_1") (pintype "bidirectional"))
      (node (ref "SV2") (pin "13") (pinfunction "13_13") (pintype "passive"))
    )
    (net (code "43") (name "M4.6") (class "Default")
      (node (ref "IC4") (pin "5") (pinfunction "X5_5") (pintype "bidirectional"))
      (node (ref "SV2") (pin "14") (pinfunction "14_14") (pintype "passive"))
    )
    (net (code "44") (name "M4.7") (class "Default")
      (node (ref "IC4") (pin "2") (pinfunction "X6_2") (pintype "bidirectional"))
      (node (ref "SV2") (pin "15") (pinfunction "15_15") (pintype "passive"))
    )
    (net (code "45") (name "M4.8") (class "Default")
      (node (ref "IC4") (pin "4") (pinfunction "X7_4") (pintype "bidirectional"))
      (node (ref "SV2") (pin "16") (pinfunction "16_16") (pintype "passive"))
    )
    (net (code "46") (name "N1") (class "Default")
      (node (ref "C6") (pin "1") (pinfunction "1_1") (pintype "passive"))
      (node (ref "C7") (pin "1") (pinfunction "1_1") (pintype "passive"))
      (node (ref "IC1") (pin "20") (pinfunction "VCC_20") (pintype "power_in"))
      (node (ref "IC1") (pin "4") (pinfunction "VCCIO_4") (pintype "power_in"))
      (node (ref "L1") (pin "2") (pinfunction "2_2") (pintype "passive"))
    )
    (net (code "47") (name "Net-(C16-Pad1)") (class "Default")
      (node (ref "C16") (pin "1") (pinfunction "1_1") (pintype "passive"))
      (node (ref "U$1") (pin "20") (pinfunction "20_20") (pintype "power_in"))
    )
    (net (code "48") (name "Net-(IC1-3V3OUT)") (class "Default")
      (node (ref "C8") (pin "1") (pinfunction "1_1") (pintype "passive"))
      (node (ref "IC1") (pin "17") (pinfunction "3V3OUT_17") (pintype "output"))
    )
    (net (code "49") (name "Net-(IC1-CBUS0)") (class "Default")
      (node (ref "IC1") (pin "23") (pinfunction "CBUS0_23") (pintype "bidirectional"))
      (node (ref "R7") (pin "1") (pinfunction "1_1") (pintype "passive"))
    )
    (net (code "50") (name "Net-(IC1-CBUS1)") (class "Default")
      (node (ref "IC1") (pin "22") (pinfunction "CBUS1_22") (pintype "bidirectional"))
      (node (ref "R8") (pin "1") (pinfunction "1_1") (pintype "passive"))
    )
    (net (code "51") (name "Net-(IC1-RXD)") (class "Default")
      (node (ref "IC1") (pin "5") (pinfunction "RXD_5") (pintype "input"))
      (node (ref "RX") (pin "1") (pinfunction "1_1") (pintype "passive"))
    )
    (net (code "52") (name "Net-(IC1-TXD)") (class "Default")
      (node (ref "IC1") (pin "1") (pinfunction "TXD_1") (pintype "output"))
      (node (ref "TX") (pin "1") (pinfunction "1_1") (pintype "passive"))
    )
    (net (code "53") (name "Net-(LED1-PadC)") (class "Default")
      (node (ref "LED1") (pin "C") (pinfunction "C_C") (pintype "passive"))
      (node (ref "R7") (pin "2") (pinfunction "2_2") (pintype "passive"))
    )
    (net (code "54") (name "Net-(LED2-PadC)") (class "Default")
      (node (ref "LED2") (pin "C") (pinfunction "C_C") (pintype "passive"))
      (node (ref "R8") (pin "2") (pinfunction "2_2") (pintype "passive"))
    )
    (net (code "55") (name "OM1") (class "Default")
      (node (ref "IC3") (pin "11") (pinfunction "A_11") (pintype "input"))
      (node (ref "IC4") (pin "11") (pinfunction "A_11") (pintype "input"))
      (node (ref "IC8") (pin "11") (pinfunction "A_11") (pintype "input"))
      (node (ref "IC9") (pin "11") (pinfunction "A_11") (pintype "input"))
      (node (ref "U$1") (pin "25") (pinfunction "25_25") (pintype "bidirectional"))
    )
    (net (code "56") (name "OM2") (class "Default")
      (node (ref "IC3") (pin "10") (pinfunction "B_10") (pintype "input"))
      (node (ref "IC4") (pin "10") (pinfunction "B_10") (pintype "input"))
      (node (ref "IC8") (pin "10") (pinfunction "B_10") (pintype "input"))
      (node (ref "IC9") (pin "10") (pinfunction "B_10") (pintype "input"))
      (node (ref "U$1") (pin "26") (pinfunction "26_26") (pintype "bidirectional"))
    )
    (net (code "57") (name "OM3") (class "Default")
      (node (ref "IC3") (pin "9") (pinfunction "C_9") (pintype "input"))
      (node (ref "IC4") (pin "9") (pinfunction "C_9") (pintype "input"))
      (node (ref "IC8") (pin "9") (pinfunction "C_9") (pintype "input"))
      (node (ref "IC9") (pin "9") (pinfunction "C_9") (pintype "input"))
      (node (ref "U$1") (pin "27") (pinfunction "27_27") (pintype "bidirectional"))
    )
    (net (code "58") (name "OS1") (class "Default")
      (node (ref "IC5") (pin "11") (pinfunction "SCK_11") (pintype "input"))
      (node (ref "IC6") (pin "11") (pinfunction "SCK_11") (pintype "input"))
      (node (ref "IC7") (pin "11") (pinfunction "SCK_11") (pintype "input"))
      (node (ref "U$1") (pin "80") (pinfunction "80_80") (pintype "bidirectional"))
    )
    (net (code "59") (name "OS2") (class "Default")
      (node (ref "IC5") (pin "14") (pinfunction "SER_14") (pintype "input"))
      (node (ref "U$1") (pin "77") (pinfunction "77_77") (pintype "bidirectional"))
    )
    (net (code "60") (name "OS3") (class "Default")
      (node (ref "IC5") (pin "12") (pinfunction "RCK_12") (pintype "input"))
      (node (ref "IC6") (pin "12") (pinfunction "RCK_12") (pintype "input"))
      (node (ref "IC7") (pin "12") (pinfunction "RCK_12") (pintype "input"))
      (node (ref "U$1") (pin "79") (pinfunction "79_79") (pintype "bidirectional"))
    )
    (net (code "61") (name "OS4") (class "Default")
      (node (ref "IC5") (pin "10") (pinfunction "SCL_10") (pintype "input"))
      (node (ref "IC6") (pin "10") (pinfunction "SCL_10") (pintype "input"))
      (node (ref "IC7") (pin "10") (pinfunction "SCL_10") (pintype "input"))
      (node (ref "U$1") (pin "5") (pinfunction "5_5") (pintype "bidirectional"))
    )
    (net (code "62") (name "OS5") (class "Default")
      (node (ref "IC5") (pin "13") (pinfunction "G_13") (pintype "input"))
      (node (ref "IC6") (pin "13") (pinfunction "G_13") (pintype "input"))
      (node (ref "IC7") (pin "13") (pinfunction "G_13") (pintype "input"))
      (node (ref "U$1") (pin "78") (pinfunction "78_78") (pintype "bidirectional"))
    )
    (net (code "63") (name "P3.3") (class "Default")
      (node (ref "RX") (pin "2") (pinfunction "2_2") (pintype "passive"))
      (node (ref "U$1") (pin "40") (pinfunction "40_40") (pintype "bidirectional"))
    )
    (net (code "64") (name "P3.4") (class "Default")
      (node (ref "TX") (pin "2") (pinfunction "2_2") (pintype "passive"))
      (node (ref "U$1") (pin "41") (pinfunction "41_41") (pintype "bidirectional"))
    )
    (net (code "65") (name "RST{slash}SBWTDIO") (class "Default")
      (node (ref "C17") (pin "1") (pinfunction "1_1") (pintype "passive"))
      (node (ref "R16") (pin "1") (pinfunction "1_1") (pintype "passive"))
      (node (ref "RESET") (pin "1") (pinfunction "S_1") (pintype "passive"))
      (node (ref "RESET") (pin "2") (pinfunction "S1_2") (pintype "passive"))
      (node (ref "SPI-BI-WIRE") (pin "3") (pinfunction "3_3") (pintype "passive"))
      (node (ref "U$1") (pin "76") (pinfunction "76_76") (pintype "bidirectional"))
    )
    (net (code "66") (name "S1.1") (class "Default")
      (node (ref "COLUMNS") (pin "1") (pinfunction "1_1") (pintype "passive"))
      (node (ref "IC5") (pin "15") (pinfunction "QA_15") (pintype "tri_state"))
    )
    (net (code "67") (name "S1.2") (class "Default")
      (node (ref "COLUMNS") (pin "2") (pinfunction "2_2") (pintype "passive"))
      (node (ref "IC5") (pin "1") (pinfunction "QB_1") (pintype "tri_state"))
    )
    (net (code "68") (name "S1.3") (class "Default")
      (node (ref "COLUMNS") (pin "3") (pinfunction "3_3") (pintype "passive"))
      (node (ref "IC5") (pin "2") (pinfunction "QC_2") (pintype "tri_state"))
    )
    (net (code "69") (name "S1.4") (class "Default")
      (node (ref "COLUMNS") (pin "4") (pinfunction "4_4") (pintype "passive"))
      (node (ref "IC5") (pin "3") (pinfunction "QD_3") (pintype "tri_state"))
    )
    (net (code "70") (name "S1.5") (class "Default")
      (node (ref "COLUMNS") (pin "5") (pinfunction "5_5") (pintype "passive"))
      (node (ref "IC5") (pin "4") (pinfunction "QE_4") (pintype "tri_state"))
    )
    (net (code "71") (name "S1.6") (class "Default")
      (node (ref "COLUMNS") (pin "6") (pinfunction "6_6") (pintype "passive"))
      (node (ref "IC5") (pin "5") (pinfunction "QF_5") (pintype "tri_state"))
    )
    (net (code "72") (name "S1.7") (class "Default")
      (node (ref "COLUMNS") (pin "7") (pinfunction "7_7") (pintype "passive"))
      (node (ref "IC5") (pin "6") (pinfunction "QG_6") (pintype "tri_state"))
    )
    (net (code "73") (name "S1.8") (class "Default")
      (node (ref "COLUMNS") (pin "8") (pinfunction "8_8") (pintype "passive"))
      (node (ref "IC5") (pin "7") (pinfunction "QH_7") (pintype "tri_state"))
    )
    (net (code "74") (name "S2.1") (class "Default")
      (node (ref "COLUMNS") (pin "9") (pinfunction "9_9") (pintype "passive"))
      (node (ref "IC6") (pin "15") (pinfunction "QA_15") (pintype "tri_state"))
    )
    (net (code "75") (name "S2.2") (class "Default")
      (node (ref "COLUMNS") (pin "10") (pinfunction "10_10") (pintype "passive"))
      (node (ref "IC6") (pin "1") (pinfunction "QB_1") (pintype "tri_state"))
    )
    (net (code "76") (name "S2.3") (class "Default")
      (node (ref "COLUMNS") (pin "11") (pinfunction "11_11") (pintype "passive"))
      (node (ref "IC6") (pin "2") (pinfunction "QC_2") (pintype "tri_state"))
    )
    (net (code "77") (name "S2.4") (class "Default")
      (node (ref "COLUMNS") (pin "12") (pinfunction "12_12") (pintype "passive"))
      (node (ref "IC6") (pin "3") (pinfunction "QD_3") (pintype "tri_state"))
    )
    (net (code "78") (name "S2.5") (class "Default")
      (node (ref "COLUMNS") (pin "13") (pinfunction "13_13") (pintype "passive"))
      (node (ref "IC6") (pin "4") (pinfunction "QE_4") (pintype "tri_state"))
    )
    (net (code "79") (name "S2.6") (class "Default")
      (node (ref "COLUMNS") (pin "14") (pinfunction "14_14") (pintype "passive"))
      (node (ref "IC6") (pin "5") (pinfunction "QF_5") (pintype "tri_state"))
    )
    (net (code "80") (name "S2.7") (class "Default")
      (node (ref "COLUMNS") (pin "15") (pinfunction "15_15") (pintype "passive"))
      (node (ref "IC6") (pin "6") (pinfunction "QG_6") (pintype "tri_state"))
    )
    (net (code "81") (name "S2.8") (class "Default")
      (node (ref "COLUMNS") (pin "16") (pinfunction "16_16") (pintype "passive"))
      (node (ref "IC6") (pin "7") (pinfunction "QH_7") (pintype "tri_state"))
    )
    (net (code "82") (name "S3.1") (class "Default")
      (node (ref "COLUMNS") (pin "17") (pinfunction "17_17") (pintype "passive"))
      (node (ref "IC7") (pin "15") (pinfunction "QA_15") (pintype "tri_state"))
    )
    (net (code "83") (name "S3.2") (class "Default")
      (node (ref "COLUMNS") (pin "18") (pinfunction "18_18") (pintype "passive"))
      (node (ref "IC7") (pin "1") (pinfunction "QB_1") (pintype "tri_state"))
    )
    (net (code "84") (name "S3.3") (class "Default")
      (node (ref "COLUMNS") (pin "19") (pinfunction "19_19") (pintype "passive"))
      (node (ref "IC7") (pin "2") (pinfunction "QC_2") (pintype "tri_state"))
    )
    (net (code "85") (name "S3.4") (class "Default")
      (node (ref "COLUMNS") (pin "20") (pinfunction "20_20") (pintype "passive"))
      (node (ref "IC7") (pin "3") (pinfunction "QD_3") (pintype "tri_state"))
    )
    (net (code "86") (name "S3.5") (class "Default")
      (node (ref "COLUMNS") (pin "21") (pinfunction "21_21") (pintype "passive"))
      (node (ref "IC7") (pin "4") (pinfunction "QE_4") (pintype "tri_state"))
    )
    (net (code "87") (name "S3.6") (class "Default")
      (node (ref "COLUMNS") (pin "22") (pinfunction "22_22") (pintype "passive"))
      (node (ref "IC7") (pin "5") (pinfunction "QF_5") (pintype "tri_state"))
    )
    (net (code "88") (name "S3.7") (class "Default")
      (node (ref "COLUMNS") (pin "23") (pinfunction "23_23") (pintype "passive"))
      (node (ref "IC7") (pin "6") (pinfunction "QG_6") (pintype "tri_state"))
    )
    (net (code "89") (name "S3.8") (class "Default")
      (node (ref "COLUMNS") (pin "24") (pinfunction "24_24") (pintype "passive"))
      (node (ref "IC7") (pin "7") (pinfunction "QH_7") (pintype "tri_state"))
    )
    (net (code "90") (name "TEST{slash}SBWTCK") (class "Default")
      (node (ref "SPI-BI-WIRE") (pin "2") (pinfunction "2_2") (pintype "passive"))
      (node (ref "U$1") (pin "71") (pinfunction "71_71") (pintype "input"))
    )
    (net (code "91") (name "USB_D+") (class "Default")
      (node (ref "C4") (pin "1") (pinfunction "1_1") (pintype "passive"))
      (node (ref "IC1") (pin "15") (pinfunction "USBDP_15") (pintype "bidirectional"))
      (node (ref "R6") (pin "2") (pinfunction "2_2") (pintype "passive"))
    )
    (net (code "92") (name "USB_D-") (class "Default")
      (node (ref "C3") (pin "1") (pinfunction "1_1") (pintype "passive"))
      (node (ref "IC1") (pin "16") (pinfunction "USBDM_16") (pintype "bidirectional"))
      (node (ref "R5") (pin "2") (pinfunction "2_2") (pintype "passive"))
    )
    (net (code "93") (name "X0") (class "Default")
      (node (ref "IC5") (pin "9") (pinfunction "QH*_9") (pintype "tri_state"))
      (node (ref "IC6") (pin "14") (pinfunction "SER_14") (pintype "input"))
    )
    (net (code "94") (name "X1") (class "Default")
      (node (ref "IC6") (pin "9") (pinfunction "QH*_9") (pintype "tri_state"))
      (node (ref "IC7") (pin "14") (pinfunction "SER_14") (pintype "input"))
    )
    (net (code "95") (name "unconnected-(IC1-CBUS2-Pad13)") (class "Default")
      (node (ref "IC1") (pin "13") (pinfunction "CBUS2_13") (pintype "bidirectional"))
    )
    (net (code "96") (name "unconnected-(IC1-CBUS3-Pad14)") (class "Default")
      (node (ref "IC1") (pin "14") (pinfunction "CBUS3_14") (pintype "bidirectional"))
    )
    (net (code "97") (name "unconnected-(IC1-CBUS4-Pad12)") (class "Default")
      (node (ref "IC1") (pin "12") (pinfunction "CBUS4_12") (pintype "bidirectional"))
    )
    (net (code "98") (name "unconnected-(IC1-OSCI-Pad27)") (class "Default")
      (node (ref "IC1") (pin "27") (pinfunction "OSCI_27") (pintype "input"))
    )
    (net (code "99") (name "unconnected-(IC1-OSCO-Pad28)") (class "Default")
      (node (ref "IC1") (pin "28") (pinfunction "OSCO_28") (pintype "output"))
    )
    (net (code "100") (name "unconnected-(IC1-~{CTS}-Pad11)") (class "Default")
      (node (ref "IC1") (pin "11") (pinfunction "~{CTS}_11") (pintype "input"))
    )
    (net (code "101") (name "unconnected-(IC1-~{DCD}-Pad10)") (class "Default")
      (node (ref "IC1") (pin "10") (pinfunction "~{DCD}_10") (pintype "input"))
    )
    (net (code "102") (name "unconnected-(IC1-~{DSR}-Pad9)") (class "Default")
      (node (ref "IC1") (pin "9") (pinfunction "~{DSR}_9") (pintype "input"))
    )
    (net (code "103") (name "unconnected-(IC1-~{DTR}-Pad2)") (class "Default")
      (node (ref "IC1") (pin "2") (pinfunction "~{DTR}_2") (pintype "output"))
    )
    (net (code "104") (name "unconnected-(IC1-~{RESET}-Pad19)") (class "Default")
      (node (ref "IC1") (pin "19") (pinfunction "~{RESET}_19") (pintype "input"))
    )
    (net (code "105") (name "unconnected-(IC1-~{RI}-Pad6)") (class "Default")
      (node (ref "IC1") (pin "6") (pinfunction "~{RI}_6") (pintype "input"))
    )
    (net (code "106") (name "unconnected-(IC1-~{RTS}-Pad3)") (class "Default")
      (node (ref "IC1") (pin "3") (pinfunction "~{RTS}_3") (pintype "output"))
    )
    (net (code "107") (name "unconnected-(IC7A-QH*-Pad9)") (class "Default")
      (node (ref "IC7") (pin "9") (pinfunction "QH*_9") (pintype "tri_state"))
    )
    (net (code "108") (name "unconnected-(U$1-Pad6)") (class "Default")
      (node (ref "U$1") (pin "6") (pinfunction "6_6") (pintype "bidirectional"))
    )
    (net (code "109") (name "unconnected-(U$1-Pad7)") (class "Default")
      (node (ref "U$1") (pin "7") (pinfunction "7_7") (pintype "bidirectional"))
    )
    (net (code "110") (name "unconnected-(U$1-Pad8)") (class "Default")
      (node (ref "U$1") (pin "8") (pinfunction "8_8") (pintype "bidirectional"))
    )
    (net (code "111") (name "unconnected-(U$1-Pad9)") (class "Default")
      (node (ref "U$1") (pin "9") (pinfunction "9_9") (pintype "bidirectional"))
    )
    (net (code "112") (name "unconnected-(U$1-Pad10)") (class "Default")
      (node (ref "U$1") (pin "10") (pinfunction "10_10") (pintype "bidirectional"))
    )
    (net (code "113") (name "unconnected-(U$1-Pad12)") (class "Default")
      (node (ref "U$1") (pin "12") (pinfunction "12_12") (pintype "bidirectional"))
    )
    (net (code "114") (name "unconnected-(U$1-Pad13)") (class "Default")
      (node (ref "U$1") (pin "13") (pinfunction "13_13") (pintype "bidirectional"))
    )
    (net (code "115") (name "unconnected-(U$1-Pad15)") (class "Default")
      (node (ref "U$1") (pin "15") (pinfunction "15_15") (pintype "bidirectional"))
    )
    (net (code "116") (name "unconnected-(U$1-Pad16)") (class "Default")
      (node (ref "U$1") (pin "16") (pinfunction "16_16") (pintype "bidirectional"))
    )
    (net (code "117") (name "unconnected-(U$1-Pad17)") (class "Default")
      (node (ref "U$1") (pin "17") (pinfunction "17_17") (pintype "bidirectional"))
    )
    (net (code "118") (name "unconnected-(U$1-Pad21)") (class "Default")
      (node (ref "U$1") (pin "21") (pinfunction "21_21") (pintype "bidirectional"))
    )
    (net (code "119") (name "unconnected-(U$1-Pad22)") (class "Default")
      (node (ref "U$1") (pin "22") (pinfunction "22_22") (pintype "bidirectional"))
    )
    (net (code "120") (name "unconnected-(U$1-Pad23)") (class "Default")
      (node (ref "U$1") (pin "23") (pinfunction "23_23") (pintype "bidirectional"))
    )
    (net (code "121") (name "unconnected-(U$1-Pad24)") (class "Default")
      (node (ref "U$1") (pin "24") (pinfunction "24_24") (pintype "bidirectional"))
    )
    (net (code "122") (name "unconnected-(U$1-Pad28)") (class "Default")
      (node (ref "U$1") (pin "28") (pinfunction "28_28") (pintype "bidirectional"))
    )
    (net (code "123") (name "unconnected-(U$1-Pad29)") (class "Default")
      (node (ref "U$1") (pin "29") (pinfunction "29_29") (pintype "bidirectional"))
    )
    (net (code "124") (name "unconnected-(U$1-Pad30)") (class "Default")
      (node (ref "U$1") (pin "30") (pinfunction "30_30") (pintype "bidirectional"))
    )
    (net (code "125") (name "unconnected-(U$1-Pad31)") (class "Default")
      (node (ref "U$1") (pin "31") (pinfunction "31_31") (pintype "bidirectional"))
    )
    (net (code "126") (name "unconnected-(U$1-Pad32)") (class "Default")
      (node (ref "U$1") (pin "32") (pinfunction "32_32") (pintype "bidirectional"))
    )
    (net (code "127") (name "unconnected-(U$1-Pad33)") (class "Default")
      (node (ref "U$1") (pin "33") (pinfunction "33_33") (pintype "bidirectional"))
    )
    (net (code "128") (name "unconnected-(U$1-Pad34)") (class "Default")
      (node (ref "U$1") (pin "34") (pinfunction "34_34") (pintype "bidirectional"))
    )
    (net (code "129") (name "unconnected-(U$1-Pad35)") (class "Default")
      (node (ref "U$1") (pin "35") (pinfunction "35_35") (pintype "bidirectional"))
    )
    (net (code "130") (name "unconnected-(U$1-Pad36)") (class "Default")
      (node (ref "U$1") (pin "36") (pinfunction "36_36") (pintype "bidirectional"))
    )
    (net (code "131") (name "unconnected-(U$1-Pad37)") (class "Default")
      (node (ref "U$1") (pin "37") (pinfunction "37_37") (pintype "bidirectional"))
    )
    (net (code "132") (name "unconnected-(U$1-Pad38)") (class "Default")
      (node (ref "U$1") (pin "38") (pinfunction "38_38") (pintype "bidirectional"))
    )
    (net (code "133") (name "unconnected-(U$1-Pad39)") (class "Default")
      (node (ref "U$1") (pin "39") (pinfunction "39_39") (pintype "bidirectional"))
    )
    (net (code "134") (name "unconnected-(U$1-Pad42)") (class "Default")
      (node (ref "U$1") (pin "42") (pinfunction "42_42") (pintype "bidirectional"))
    )
    (net (code "135") (name "unconnected-(U$1-Pad43)") (class "Default")
      (node (ref "U$1") (pin "43") (pinfunction "43_43") (pintype "bidirectional"))
    )
    (net (code "136") (name "unconnected-(U$1-Pad44)") (class "Default")
      (node (ref "U$1") (pin "44") (pinfunction "44_44") (pintype "bidirectional"))
    )
    (net (code "137") (name "unconnected-(U$1-Pad45)") (class "Default")
      (node (ref "U$1") (pin "45") (pinfunction "45_45") (pintype "bidirectional"))
    )
    (net (code "138") (name "unconnected-(U$1-Pad46)") (class "Default")
      (node (ref "U$1") (pin "46") (pinfunction "46_46") (pintype "bidirectional"))
    )
    (net (code "139") (name "unconnected-(U$1-Pad47)") (class "Default")
      (node (ref "U$1") (pin "47") (pinfunction "47_47") (pintype "bidirectional"))
    )
    (net (code "140") (name "unconnected-(U$1-Pad48)") (class "Default")
      (node (ref "U$1") (pin "48") (pinfunction "48_48") (pintype "bidirectional"))
    )
    (net (code "141") (name "unconnected-(U$1-Pad51)") (class "Default")
      (node (ref "U$1") (pin "51") (pinfunction "51_51") (pintype "bidirectional"))
    )
    (net (code "142") (name "unconnected-(U$1-Pad52)") (class "Default")
      (node (ref "U$1") (pin "52") (pinfunction "52_52") (pintype "bidirectional"))
    )
    (net (code "143") (name "unconnected-(U$1-Pad53)") (class "Default")
      (node (ref "U$1") (pin "53") (pinfunction "53_53") (pintype "bidirectional"))
    )
    (net (code "144") (name "unconnected-(U$1-Pad54)") (class "Default")
      (node (ref "U$1") (pin "54") (pinfunction "54_54") (pintype "bidirectional"))
    )
    (net (code "145") (name "unconnected-(U$1-Pad55)") (class "Default")
      (node (ref "U$1") (pin "55") (pinfunction "55_55") (pintype "bidirectional"))
    )
    (net (code "146") (name "unconnected-(U$1-Pad56)") (class "Default")
      (node (ref "U$1") (pin "56") (pinfunction "56_56") (pintype "bidirectional"))
    )
    (net (code "147") (name "unconnected-(U$1-Pad57)") (class "Default")
      (node (ref "U$1") (pin "57") (pinfunction "57_57") (pintype "bidirectional"))
    )
    (net (code "148") (name "unconnected-(U$1-Pad58)") (class "Default")
      (node (ref "U$1") (pin "58") (pinfunction "58_58") (pintype "bidirectional"))
    )
    (net (code "149") (name "unconnected-(U$1-Pad59)") (class "Default")
      (node (ref "U$1") (pin "59") (pinfunction "59_59") (pintype "bidirectional"))
    )
    (net (code "150") (name "unconnected-(U$1-Pad60)") (class "Default")
      (node (ref "U$1") (pin "60") (pinfunction "60_60") (pintype "bidirectional"))
    )
    (net (code "151") (name "unconnected-(U$1-Pad62)") (class "Default")
      (node (ref "U$1") (pin "62") (pinfunction "62_62") (pintype "bidirectional"))
    )
    (net (code "152") (name "unconnected-(U$1-Pad63)") (class "Default")
      (node (ref "U$1") (pin "63") (pinfunction "63_63") (pintype "bidirectional"))
    )
    (net (code "153") (name "unconnected-(U$1-Pad64)") (class "Default")
      (node (ref "U$1") (pin "64") (pinfunction "64_64") (pintype "bidirectional"))
    )
    (net (code "154") (name "unconnected-(U$1-Pad69)") (class "Default")
      (node (ref "U$1") (pin "69") (pinfunction "69_69") (pintype "bidirectional"))
    )
    (net (code "155") (name "unconnected-(U$1-Pad70)") (class "Default")
      (node (ref "U$1") (pin "70") (pinfunction "70_70") (pintype "bidirectional"))
    )
    (net (code "156") (name "unconnected-(U$1-Pad72)") (class "Default")
      (node (ref "U$1") (pin "72") (pinfunction "72_72") (pintype "bidirectional"))
    )
    (net (code "157") (name "unconnected-(U$1-Pad73)") (class "Default")
      (node (ref "U$1") (pin "73") (pinfunction "73_73") (pintype "bidirectional"))
    )
    (net (code "158") (name "unconnected-(U$1-Pad74)") (class "Default")
      (node (ref "U$1") (pin "74") (pinfunction "74_74") (pintype "bidirectional"))
    )
    (net (code "159") (name "unconnected-(U$1-Pad75)") (class "Default")
      (node (ref "U$1") (pin "75") (pinfunction "75_75") (pintype "bidirectional"))
    )
    (net (code "160") (name "unconnected-(U$2-NC-PadP2)") (class "Default")
      (node (ref "U$2") (pin "P2") (pinfunction "NC_P2") (pintype "bidirectional"))
    )
  )
)
